# SurfaceEEG_V1_3.net
KiCad netlist of a schematic drawn in EAGLE
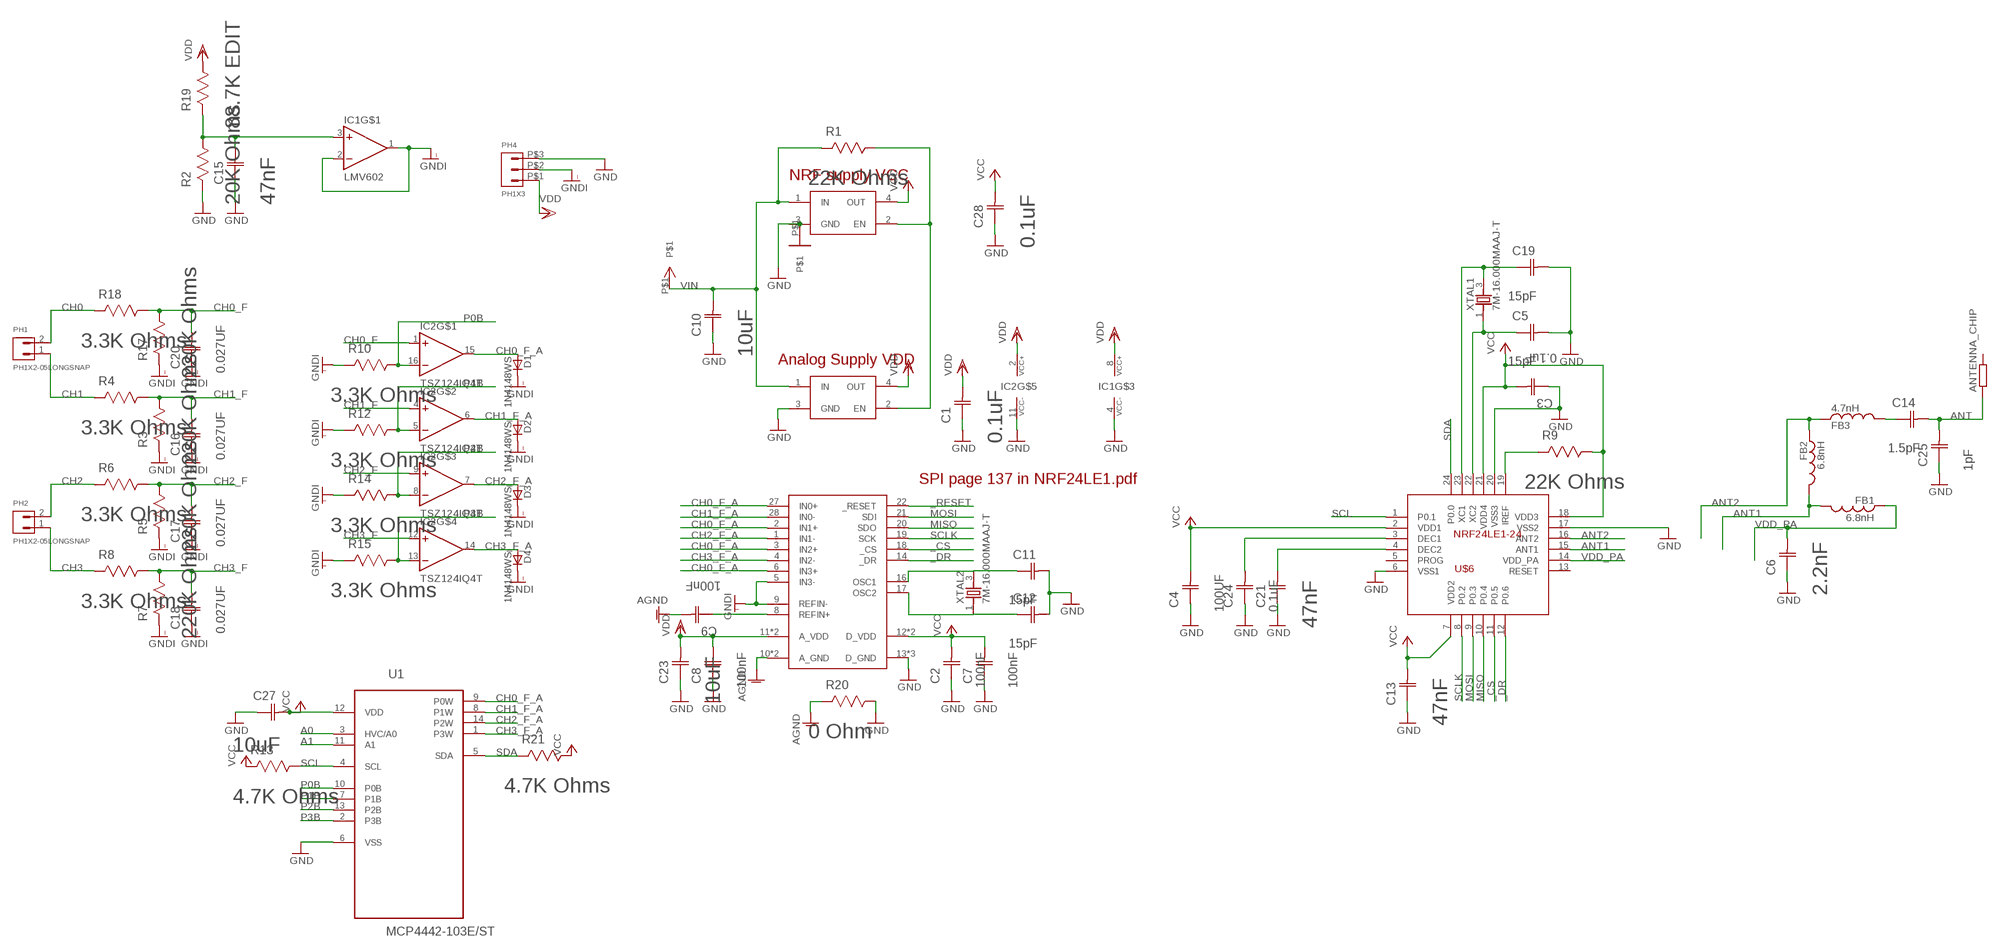
[diagram p0: schematic, sheet 1]

(export (version "E")
  (design (tool "Eeschema 10.0.6"))
  (components
    (comp (ref "ANTENNA_CHIP")
      (value "R0805")
      (footprint "eagle-import:R0805")
      (libsource (lib "eagle-import") (part "R0805"))
    )
    (comp (ref "C1")
      (value "0.1uF")
      (footprint "eagle-import:CAPC1608X85N")
      (fields (field (name "MPN") "C0603C104K5RAC-TU") (field (name "TOLERANCE") "±10%"))
      (libsource (lib "eagle-import") (part "C0603C104K5RAC-TU"))
    )
    (comp (ref "C2")
      (value "100nF")
      (footprint "eagle-import:CAPC1608X90N")
      (fields (field (name "MPN") "06033C104JAT2A") (field (name "TOLERANCE") "±5%"))
      (libsource (lib "eagle-import") (part "06033C104JAT2A"))
    )
    (comp (ref "C3")
      (value "0.1uF")
      (footprint "eagle-import:CAPC1005X60N")
      (fields (field (name "MPN") "04023C104KAT2A") (field (name "TOLERANCE") "±10%"))
      (libsource (lib "eagle-import") (part "04023C104KAT2A"))
    )
    (comp (ref "C4")
      (value "100UF")
      (footprint "eagle-import:CAPC3216X178N")
      (fields (field (name "MPN") "1206YD106MAT2A") (field (name "TOLERANCE") "±20%"))
      (libsource (lib "eagle-import") (part "1206YD106MAT2A"))
    )
    (comp (ref "C5")
      (value "15pF")
      (footprint "eagle-import:CAPC1005X60N")
      (fields (field (name "MPN") "UQCL2A150JAT2A/500") (field (name "TOLERANCE") "±5%"))
      (libsource (lib "eagle-import") (part "UQCL2A150JAT2A/500"))
    )
    (comp (ref "C6")
      (value "2.2nF")
      (footprint "eagle-import:CAPC1005X60N")
      (fields (field (name "MPN") "C0402C222K5RACTU") (field (name "TOLERANCE") "±10%"))
      (libsource (lib "eagle-import") (part "C0402C222K5RACTU"))
    )
    (comp (ref "C7")
      (value "100nF")
      (footprint "eagle-import:CAPC1608X90N")
      (fields (field (name "MPN") "06033C104JAT2A") (field (name "TOLERANCE") "±5%"))
      (libsource (lib "eagle-import") (part "06033C104JAT2A"))
    )
    (comp (ref "C8")
      (value "100nF")
      (footprint "eagle-import:CAPC1608X90N")
      (fields (field (name "MPN") "06033C104JAT2A") (field (name "TOLERANCE") "±5%"))
      (libsource (lib "eagle-import") (part "06033C104JAT2A"))
    )
    (comp (ref "C9")
      (value "100nF")
      (footprint "eagle-import:CAPC1608X90N")
      (fields (field (name "MPN") "06033C104JAT2A") (field (name "TOLERANCE") "±5%"))
      (libsource (lib "eagle-import") (part "06033C104JAT2A"))
    )
    (comp (ref "C10")
      (value "10uF")
      (footprint "eagle-import:CAPC1608X85N")
      (fields (field (name "MPN") "C0603C106M9PACTU") (field (name "TOLERANCE") "±20%"))
      (libsource (lib "eagle-import") (part "C0603C106M9PACTU"))
    )
    (comp (ref "C11")
      (value "15pF")
      (footprint "eagle-import:CAPC1005X60N")
      (fields (field (name "MPN") "UQCL2A150JAT2A/500") (field (name "TOLERANCE") "±5%"))
      (libsource (lib "eagle-import") (part "UQCL2A150JAT2A/500"))
    )
    (comp (ref "C12")
      (value "15pF")
      (footprint "eagle-import:CAPC1005X60N")
      (fields (field (name "MPN") "UQCL2A150JAT2A/500") (field (name "TOLERANCE") "±5%"))
      (libsource (lib "eagle-import") (part "UQCL2A150JAT2A/500"))
    )
    (comp (ref "C13")
      (value "47nF")
      (footprint "eagle-import:CAPC1608X85N")
      (fields (field (name "MPN") "C0603C473K1RACTU") (field (name "TOLERANCE") "±10%"))
      (libsource (lib "eagle-import") (part "C0603C473K1RACTU"))
    )
    (comp (ref "C14")
      (value "1.5pF")
      (footprint "eagle-import:CAPC1005X60N")
      (fields (field (name "MPN") "UQCL2A1R5BAT2A/500") (field (name "TOLERANCE") "±.1 pF"))
      (libsource (lib "eagle-import") (part "UQCL2A1R5BAT2A/500"))
    )
    (comp (ref "C15")
      (value "47nF")
      (footprint "eagle-import:CAPC1608X85N")
      (fields (field (name "MPN") "C0603C473K1RACTU") (field (name "TOLERANCE") "±10%"))
      (libsource (lib "eagle-import") (part "C0603C473K1RACTU"))
    )
    (comp (ref "C16")
      (value "0.027UF")
      (footprint "eagle-import:CAPC1608X90N")
      (fields (field (name "MPN") "0603YC273JAT2A") (field (name "TOLERANCE") "±5%"))
      (libsource (lib "eagle-import") (part "0603YC273JAT2A"))
    )
    (comp (ref "C17")
      (value "0.027UF")
      (footprint "eagle-import:CAPC1608X90N")
      (fields (field (name "MPN") "0603YC273JAT2A") (field (name "TOLERANCE") "±5%"))
      (libsource (lib "eagle-import") (part "0603YC273JAT2A"))
    )
    (comp (ref "C18")
      (value "0.027UF")
      (footprint "eagle-import:CAPC1608X90N")
      (fields (field (name "MPN") "0603YC273JAT2A") (field (name "TOLERANCE") "±5%"))
      (libsource (lib "eagle-import") (part "0603YC273JAT2A"))
    )
    (comp (ref "C19")
      (value "15pF")
      (footprint "eagle-import:CAPC1005X60N")
      (fields (field (name "MPN") "UQCL2A150JAT2A/500") (field (name "TOLERANCE") "±5%"))
      (libsource (lib "eagle-import") (part "UQCL2A150JAT2A/500"))
    )
    (comp (ref "C20")
      (value "0.027UF")
      (footprint "eagle-import:CAPC1608X90N")
      (fields (field (name "MPN") "0603YC273JAT2A") (field (name "TOLERANCE") "±5%"))
      (libsource (lib "eagle-import") (part "0603YC273JAT2A"))
    )
    (comp (ref "C21")
      (value "47nF")
      (footprint "eagle-import:CAPC1608X85N")
      (fields (field (name "MPN") "C0603C473K1RACTU") (field (name "TOLERANCE") "±10%"))
      (libsource (lib "eagle-import") (part "C0603C473K1RACTU"))
    )
    (comp (ref "C23")
      (value "10uF")
      (footprint "eagle-import:CAPC1608X85N")
      (fields (field (name "MPN") "C0603C106M9PACTU") (field (name "TOLERANCE") "±20%"))
      (libsource (lib "eagle-import") (part "C0603C106M9PACTU"))
    )
    (comp (ref "C24")
      (value "0.1uF")
      (footprint "eagle-import:CAPC1005X60N")
      (fields (field (name "MPN") "04023C104KAT2A") (field (name "TOLERANCE") "±10%"))
      (libsource (lib "eagle-import") (part "04023C104KAT2A"))
    )
    (comp (ref "C25")
      (value "1pF")
      (footprint "eagle-import:CAPC1005X60N")
      (fields (field (name "MPN") "UQCL2A1R0BAT2A/500") (field (name "TOLERANCE") "±.1 pF"))
      (libsource (lib "eagle-import") (part "UQCL2A1R0BAT2A/500"))
    )
    (comp (ref "C27")
      (value "10uF")
      (footprint "eagle-import:CAPC1608X85N")
      (fields (field (name "MPN") "C0603C106M9PACTU") (field (name "TOLERANCE") "±20%"))
      (libsource (lib "eagle-import") (part "C0603C106M9PACTU"))
    )
    (comp (ref "C28")
      (value "0.1uF")
      (footprint "eagle-import:CAPC1608X85N")
      (fields (field (name "MPN") "C0603C104K5RAC-TU") (field (name "TOLERANCE") "±10%"))
      (libsource (lib "eagle-import") (part "C0603C104K5RAC-TU"))
    )
    (comp (ref "D1")
      (value "1N4148WS")
      (footprint "eagle-import:SOD323F")
      (libsource (lib "eagle-import") (part "1N4148WS"))
    )
    (comp (ref "D2")
      (value "1N4148WS")
      (footprint "eagle-import:SOD323F")
      (libsource (lib "eagle-import") (part "1N4148WS"))
    )
    (comp (ref "D3")
      (value "1N4148WS")
      (footprint "eagle-import:SOD323F")
      (libsource (lib "eagle-import") (part "1N4148WS"))
    )
    (comp (ref "D4")
      (value "1N4148WS")
      (footprint "eagle-import:SOD323F")
      (libsource (lib "eagle-import") (part "1N4148WS"))
    )
    (comp (ref "FB1")
      (value "6.8nH")
      (footprint "eagle-import:FB0402")
      (libsource (lib "eagle-import") (part "FB0402"))
    )
    (comp (ref "FB2")
      (value "6.8nH")
      (footprint "eagle-import:FB0402")
      (libsource (lib "eagle-import") (part "FB0402"))
    )
    (comp (ref "FB3")
      (value "4.7nH")
      (footprint "eagle-import:FB0402")
      (libsource (lib "eagle-import") (part "FB0402"))
    )
    (comp (ref "IC1")
      (value "LMV602")
      (footprint "eagle-import:VSSOP8")
      (fields (field (name "MPN") "LMV602MM/NOPB"))
      (libsource (lib "eagle-import") (part "LMV602"))
    )
    (comp (ref "IC2")
      (value "TSZ124IQ4T")
      (footprint "eagle-import:QFN16")
      (libsource (lib "eagle-import") (part "TSZ124IQ4T"))
    )
    (comp (ref "PH1")
      (value "PH1X2-05LONGSNAP")
      (footprint "eagle-import:PHLS005-1-2")
      (libsource (lib "eagle-import") (part "PH1X2-05LONGSNAP"))
    )
    (comp (ref "PH2")
      (value "PH1X2-05LONGSNAP")
      (footprint "eagle-import:PHLS005-1-2")
      (libsource (lib "eagle-import") (part "PH1X2-05LONGSNAP"))
    )
    (comp (ref "PH4")
      (value "PH1X3")
      (footprint "eagle-import:PH005-1-3")
      (libsource (lib "eagle-import") (part "PH1X3"))
    )
    (comp (ref "R1")
      (value "22K Ohms")
      (footprint "eagle-import:RESC1608X60N")
      (fields (field (name "MPN") "RC0603FR-0722KL") (field (name "TOLERANCE") "±1%"))
      (libsource (lib "eagle-import") (part "RC0603FR-0722KL"))
    )
    (comp (ref "R2")
      (value "20K Ohms")
      (footprint "eagle-import:RESC1608X60N")
      (fields (field (name "MPN") "RC0603FR-0720KL") (field (name "TOLERANCE") "±1%"))
      (libsource (lib "eagle-import") (part "RC0603FR-0720KL"))
    )
    (comp (ref "R3")
      (value "220K Ohms")
      (footprint "eagle-import:RESC1608X60N")
      (fields (field (name "MPN") "RC0603FR-07220KL") (field (name "TOLERANCE") "±1%"))
      (libsource (lib "eagle-import") (part "RC0603FR-07220KL"))
    )
    (comp (ref "R4")
      (value "3.3K Ohms")
      (footprint "eagle-import:RESC1608X60N")
      (fields (field (name "MPN") "RC0603FR-073K3L") (field (name "TOLERANCE") "±1%"))
      (libsource (lib "eagle-import") (part "RC0603FR-073K3L"))
    )
    (comp (ref "R5")
      (value "220K Ohms")
      (footprint "eagle-import:RESC1608X60N")
      (fields (field (name "MPN") "RC0603FR-07220KL") (field (name "TOLERANCE") "±1%"))
      (libsource (lib "eagle-import") (part "RC0603FR-07220KL"))
    )
    (comp (ref "R6")
      (value "3.3K Ohms")
      (footprint "eagle-import:RESC1608X60N")
      (fields (field (name "MPN") "RC0603FR-073K3L") (field (name "TOLERANCE") "±1%"))
      (libsource (lib "eagle-import") (part "RC0603FR-073K3L"))
    )
    (comp (ref "R7")
      (value "220K Ohms")
      (footprint "eagle-import:RESC1608X60N")
      (fields (field (name "MPN") "RC0603FR-07220KL") (field (name "TOLERANCE") "±1%"))
      (libsource (lib "eagle-import") (part "RC0603FR-07220KL"))
    )
    (comp (ref "R8")
      (value "3.3K Ohms")
      (footprint "eagle-import:RESC1608X60N")
      (fields (field (name "MPN") "RC0603FR-073K3L") (field (name "TOLERANCE") "±1%"))
      (libsource (lib "eagle-import") (part "RC0603FR-073K3L"))
    )
    (comp (ref "R9")
      (value "22K Ohms")
      (footprint "eagle-import:RESC1608X60N")
      (fields (field (name "MPN") "RC0603FR-0722KL") (field (name "TOLERANCE") "±1%"))
      (libsource (lib "eagle-import") (part "RC0603FR-0722KL"))
    )
    (comp (ref "R10")
      (value "3.3K Ohms")
      (footprint "eagle-import:RESC1608X60N")
      (fields (field (name "MPN") "RC0603FR-073K3L") (field (name "TOLERANCE") "±1%"))
      (libsource (lib "eagle-import") (part "RC0603FR-073K3L"))
    )
    (comp (ref "R12")
      (value "3.3K Ohms")
      (footprint "eagle-import:RESC1608X60N")
      (fields (field (name "MPN") "RC0603FR-073K3L") (field (name "TOLERANCE") "±1%"))
      (libsource (lib "eagle-import") (part "RC0603FR-073K3L"))
    )
    (comp (ref "R13")
      (value "4.7K Ohms")
      (footprint "eagle-import:RESC1005X40N")
      (fields (field (name "MPN") "9C04021A4701JLHF3") (field (name "TOLERANCE") "±5%"))
      (libsource (lib "eagle-import") (part "9C04021A4701JLHF3"))
    )
    (comp (ref "R14")
      (value "3.3K Ohms")
      (footprint "eagle-import:RESC1608X60N")
      (fields (field (name "MPN") "RC0603FR-073K3L") (field (name "TOLERANCE") "±1%"))
      (libsource (lib "eagle-import") (part "RC0603FR-073K3L"))
    )
    (comp (ref "R15")
      (value "3.3K Ohms")
      (footprint "eagle-import:RESC1608X60N")
      (fields (field (name "MPN") "RC0603FR-073K3L") (field (name "TOLERANCE") "±1%"))
      (libsource (lib "eagle-import") (part "RC0603FR-073K3L"))
    )
    (comp (ref "R17")
      (value "220K Ohms")
      (footprint "eagle-import:RESC1608X60N")
      (fields (field (name "MPN") "RC0603FR-07220KL") (field (name "TOLERANCE") "±1%"))
      (libsource (lib "eagle-import") (part "RC0603FR-07220KL"))
    )
    (comp (ref "R18")
      (value "3.3K Ohms")
      (footprint "eagle-import:RESC1608X60N")
      (fields (field (name "MPN") "RC0603FR-073K3L") (field (name "TOLERANCE") "±1%"))
      (libsource (lib "eagle-import") (part "RC0603FR-073K3L"))
    )
    (comp (ref "R19")
      (value "88.7K EDIT")
      (footprint "eagle-import:RESC1608X60N")
      (fields (field (name "MPN") "RT0603FRE0782KL") (field (name "TOLERANCE") "±1%"))
      (libsource (lib "eagle-import") (part "RT0603FRE0782KL"))
    )
    (comp (ref "R20")
      (value "0 Ohm")
      (footprint "eagle-import:RESC1608X60N")
      (fields (field (name "MPN") "9C06031A0R00JLHFT") (field (name "TOLERANCE") "±5%"))
      (libsource (lib "eagle-import") (part "9C06031A0R00JLHFT"))
    )
    (comp (ref "R21")
      (value "4.7K Ohms")
      (footprint "eagle-import:RESC1005X40N")
      (fields (field (name "MPN") "9C04021A4701JLHF3") (field (name "TOLERANCE") "±5%"))
      (libsource (lib "eagle-import") (part "9C04021A4701JLHF3"))
    )
    (comp (ref "U$1")
      (value "NCP103")
      (footprint "eagle-import:UDFN4-1_1")
      (fields (field (name "MPN") "NCP103AMX330TCG"))
      (libsource (lib "eagle-import") (part "NCP103"))
    )
    (comp (ref "U$2")
      (value "NCP103")
      (footprint "eagle-import:UDFN4-1_1")
      (fields (field (name "MPN") "NCP103AMX330TCG"))
      (libsource (lib "eagle-import") (part "NCP103"))
    )
    (comp (ref "U$3")
      (value "MCP3912")
      (footprint "eagle-import:QFN28")
      (fields (field (name "MPN") "MCP3912A1-E/MQ "))
      (libsource (lib "eagle-import") (part "MCP3912"))
    )
    (comp (ref "U$4")
      (value "VCC")
      (footprint "eagle-import:VCC-PAD")
      (libsource (lib "eagle-import") (part "VCC"))
    )
    (comp (ref "U$5")
      (value "GND")
      (footprint "eagle-import:GND-PAD")
      (libsource (lib "eagle-import") (part "GND"))
    )
    (comp (ref "U$6")
      (value "NRF24LE1-24")
      (footprint "eagle-import:QFN24G-0.5-4X4MM")
      (fields (field (name "MPN") "NRF24LE1-F16Q24"))
      (libsource (lib "eagle-import") (part "NRF24LE1-24"))
    )
    (comp (ref "U1")
      (value "MCP4442-103E/ST")
      (footprint "eagle-import:SOP65P640X120-14N")
      (libsource (lib "eagle-import") (part "MCP4442-103E/ST"))
    )
    (comp (ref "XTAL1")
      (value "7M-16.000MAAJ-T")
      (footprint "eagle-import:TXC_7M-16.000MAAJ-T")
      (fields (field (name "MPN") "7M-16.000MAAJ-T "))
      (libsource (lib "eagle-import") (part "7M-16.000MAAJ-T"))
    )
    (comp (ref "XTAL2")
      (value "7M-16.000MAAJ-T")
      (footprint "eagle-import:TXC_7M-16.000MAAJ-T")
      (fields (field (name "MPN") "7M-16.000MAAJ-T "))
      (libsource (lib "eagle-import") (part "7M-16.000MAAJ-T"))
    )
  )
  (nets
    (net (code "1") (name "/A0") (class "Default")
      (node (ref "U1") (pin "3") (pinfunction "HVC/A0_3") (pintype "input"))
    )
    (net (code "2") (name "/A1") (class "Default")
      (node (ref "U1") (pin "11") (pinfunction "A1_11") (pintype "input"))
    )
    (net (code "3") (name "/ANT") (class "Default")
      (node (ref "ANTENNA_CHIP") (pin "1") (pinfunction "1_1") (pintype "passive"))
      (node (ref "C14") (pin "1") (pinfunction "C2_1") (pintype "passive"))
      (node (ref "C25") (pin "1") (pinfunction "C2_1") (pintype "passive"))
    )
    (net (code "4") (name "/ANT1") (class "Default")
      (node (ref "FB1") (pin "2") (pinfunction "2_2") (pintype "passive"))
      (node (ref "FB2") (pin "2") (pinfunction "2_2") (pintype "passive"))
      (node (ref "U$6") (pin "15") (pinfunction "ANT1_15") (pintype "bidirectional"))
    )
    (net (code "5") (name "/ANT2") (class "Default")
      (node (ref "FB2") (pin "1") (pinfunction "1_1") (pintype "passive"))
      (node (ref "FB3") (pin "1") (pinfunction "1_1") (pintype "passive"))
      (node (ref "U$6") (pin "16") (pinfunction "ANT2_16") (pintype "bidirectional"))
    )
    (net (code "6") (name "/CH0") (class "Default")
      (node (ref "PH1") (pin "2") (pinfunction "2_2") (pintype "bidirectional"))
      (node (ref "R18") (pin "2") (pinfunction "R2_2") (pintype "passive"))
    )
    (net (code "7") (name "/CH0_F") (class "Default")
      (node (ref "C20") (pin "2") (pinfunction "C2_2") (pintype "passive"))
      (node (ref "IC2") (pin "1") (pinfunction "IN+_1") (pintype "input"))
      (node (ref "R17") (pin "1") (pinfunction "R1_1") (pintype "passive"))
      (node (ref "R18") (pin "1") (pinfunction "R1_1") (pintype "passive"))
    )
    (net (code "8") (name "/CH0_F_A") (class "Default")
      (node (ref "D1") (pin "A") (pinfunction "A_A") (pintype "passive"))
      (node (ref "IC2") (pin "15") (pinfunction "OUT_15") (pintype "output"))
      (node (ref "U$3") (pin "2") (pinfunction "IN1+_2") (pintype "bidirectional"))
      (node (ref "U$3") (pin "27") (pinfunction "IN0+_27") (pintype "bidirectional"))
      (node (ref "U$3") (pin "3") (pinfunction "IN2+_3") (pintype "bidirectional"))
      (node (ref "U$3") (pin "6") (pinfunction "IN3+_6") (pintype "bidirectional"))
      (node (ref "U1") (pin "9") (pinfunction "P0W_9") (pintype "passive"))
    )
    (net (code "9") (name "/CH1") (class "Default")
      (node (ref "PH1") (pin "1") (pinfunction "1_1") (pintype "bidirectional"))
      (node (ref "R4") (pin "2") (pinfunction "R2_2") (pintype "passive"))
    )
    (net (code "10") (name "/CH1_F") (class "Default")
      (node (ref "C16") (pin "2") (pinfunction "C2_2") (pintype "passive"))
      (node (ref "IC2") (pin "4") (pinfunction "IN+_4") (pintype "input"))
      (node (ref "R3") (pin "1") (pinfunction "R1_1") (pintype "passive"))
      (node (ref "R4") (pin "1") (pinfunction "R1_1") (pintype "passive"))
    )
    (net (code "11") (name "/CH1_F_A") (class "Default")
      (node (ref "D2") (pin "A") (pinfunction "A_A") (pintype "passive"))
      (node (ref "IC2") (pin "6") (pinfunction "OUT_6") (pintype "output"))
      (node (ref "U$3") (pin "28") (pinfunction "IN0-_28") (pintype "bidirectional"))
      (node (ref "U1") (pin "8") (pinfunction "P1W_8") (pintype "passive"))
    )
    (net (code "12") (name "/CH2") (class "Default")
      (node (ref "PH2") (pin "2") (pinfunction "2_2") (pintype "bidirectional"))
      (node (ref "R6") (pin "2") (pinfunction "R2_2") (pintype "passive"))
    )
    (net (code "13") (name "/CH2_F") (class "Default")
      (node (ref "C17") (pin "2") (pinfunction "C2_2") (pintype "passive"))
      (node (ref "IC2") (pin "9") (pinfunction "IN+_9") (pintype "input"))
      (node (ref "R5") (pin "1") (pinfunction "R1_1") (pintype "passive"))
      (node (ref "R6") (pin "1") (pinfunction "R1_1") (pintype "passive"))
    )
    (net (code "14") (name "/CH2_F_A") (class "Default")
      (node (ref "D3") (pin "A") (pinfunction "A_A") (pintype "passive"))
      (node (ref "IC2") (pin "7") (pinfunction "OUT_7") (pintype "output"))
      (node (ref "U$3") (pin "1") (pinfunction "IN1-_1") (pintype "bidirectional"))
      (node (ref "U1") (pin "14") (pinfunction "P2W_14") (pintype "passive"))
    )
    (net (code "15") (name "/CH3") (class "Default")
      (node (ref "PH2") (pin "1") (pinfunction "1_1") (pintype "bidirectional"))
      (node (ref "R8") (pin "2") (pinfunction "R2_2") (pintype "passive"))
    )
    (net (code "16") (name "/CH3_F") (class "Default")
      (node (ref "C18") (pin "2") (pinfunction "C2_2") (pintype "passive"))
      (node (ref "IC2") (pin "12") (pinfunction "IN+_12") (pintype "input"))
      (node (ref "R7") (pin "1") (pinfunction "R1_1") (pintype "passive"))
      (node (ref "R8") (pin "1") (pinfunction "R1_1") (pintype "passive"))
    )
    (net (code "17") (name "/CH3_F_A") (class "Default")
      (node (ref "D4") (pin "A") (pinfunction "A_A") (pintype "passive"))
      (node (ref "IC2") (pin "14") (pinfunction "OUT_14") (pintype "output"))
      (node (ref "U$3") (pin "4") (pinfunction "IN2-_4") (pintype "bidirectional"))
      (node (ref "U1") (pin "1") (pinfunction "P3W_1") (pintype "passive"))
    )
    (net (code "18") (name "/MISO") (class "Default")
      (node (ref "U$3") (pin "20") (pinfunction "SDO_20") (pintype "bidirectional"))
      (node (ref "U$6") (pin "10") (pinfunction "P0.4_10") (pintype "bidirectional"))
    )
    (net (code "19") (name "/MOSI") (class "Default")
      (node (ref "U$3") (pin "21") (pinfunction "SDI_21") (pintype "bidirectional"))
      (node (ref "U$6") (pin "9") (pinfunction "P0.3_9") (pintype "bidirectional"))
    )
    (net (code "20") (name "/P0B") (class "Default")
      (node (ref "IC2") (pin "16") (pinfunction "IN-_16") (pintype "input"))
      (node (ref "R10") (pin "1") (pinfunction "R1_1") (pintype "passive"))
      (node (ref "U1") (pin "10") (pinfunction "P0B_10") (pintype "passive"))
    )
    (net (code "21") (name "/P1B") (class "Default")
      (node (ref "IC2") (pin "5") (pinfunction "IN-_5") (pintype "input"))
      (node (ref "R12") (pin "1") (pinfunction "R1_1") (pintype "passive"))
      (node (ref "U1") (pin "7") (pinfunction "P1B_7") (pintype "passive"))
    )
    (net (code "22") (name "/P2B") (class "Default")
      (node (ref "IC2") (pin "8") (pinfunction "IN-_8") (pintype "input"))
      (node (ref "R14") (pin "1") (pinfunction "R1_1") (pintype "passive"))
      (node (ref "U1") (pin "13") (pinfunction "P2B_13") (pintype "passive"))
    )
    (net (code "23") (name "/P3B") (class "Default")
      (node (ref "IC2") (pin "13") (pinfunction "IN-_13") (pintype "input"))
      (node (ref "R15") (pin "1") (pinfunction "R1_1") (pintype "passive"))
      (node (ref "U1") (pin "2") (pinfunction "P3B_2") (pintype "passive"))
    )
    (net (code "24") (name "/SCL") (class "Default")
      (node (ref "R13") (pin "1") (pinfunction "R1_1") (pintype "passive"))
      (node (ref "U$6") (pin "1") (pinfunction "P0.1_1") (pintype "bidirectional"))
      (node (ref "U1") (pin "4") (pinfunction "SCL_4") (pintype "input"))
    )
    (net (code "25") (name "/SCLK") (class "Default")
      (node (ref "U$3") (pin "19") (pinfunction "SCK_19") (pintype "bidirectional"))
      (node (ref "U$6") (pin "8") (pinfunction "P0.2_8") (pintype "bidirectional"))
    )
    (net (code "26") (name "/SDA") (class "Default")
      (node (ref "R21") (pin "2") (pinfunction "R2_2") (pintype "passive"))
      (node (ref "U$6") (pin "24") (pinfunction "P0.0_24") (pintype "bidirectional"))
      (node (ref "U1") (pin "5") (pinfunction "SDA_5") (pintype "bidirectional"))
    )
    (net (code "27") (name "/VDD_PA") (class "Default")
      (node (ref "C6") (pin "2") (pinfunction "C2_2") (pintype "passive"))
      (node (ref "FB1") (pin "1") (pinfunction "1_1") (pintype "passive"))
      (node (ref "U$6") (pin "14") (pinfunction "VDD_PA_14") (pintype "bidirectional"))
    )
    (net (code "28") (name "/VIN") (class "Default")
      (node (ref "C10") (pin "2") (pinfunction "C2_2") (pintype "passive"))
      (node (ref "R1") (pin "2") (pinfunction "R2_2") (pintype "passive"))
      (node (ref "U$1") (pin "1") (pinfunction "IN_1") (pintype "bidirectional"))
      (node (ref "U$2") (pin "1") (pinfunction "IN_1") (pintype "bidirectional"))
      (node (ref "U$4") (pin "P$1") (pinfunction "P$1_P$1") (pintype "bidirectional"))
    )
    (net (code "29") (name "/_CS") (class "Default")
      (node (ref "U$3") (pin "18") (pinfunction "_CS_18") (pintype "bidirectional"))
      (node (ref "U$6") (pin "11") (pinfunction "P0.5_11") (pintype "bidirectional"))
    )
    (net (code "30") (name "/_DR") (class "Default")
      (node (ref "U$3") (pin "14") (pinfunction "_DR_14") (pintype "bidirectional"))
      (node (ref "U$6") (pin "12") (pinfunction "P0.6_12") (pintype "bidirectional"))
    )
    (net (code "31") (name "/_RESET") (class "Default")
      (node (ref "U$3") (pin "22") (pinfunction "_RESET_22") (pintype "bidirectional"))
    )
    (net (code "32") (name "AGND") (class "Default")
      (node (ref "C9") (pin "2") (pinfunction "C2_2") (pintype "passive"))
      (node (ref "R20") (pin "2") (pinfunction "R2_2") (pintype "passive"))
      (node (ref "U$3") (pin "10") (pinfunction "A_GND_10") (pintype "bidirectional"))
      (node (ref "U$3") (pin "26") (pinfunction "A_GND_26") (pintype "bidirectional"))
    )
    (net (code "33") (name "GND") (class "Default")
      (node (ref "C1") (pin "1") (pinfunction "C1_1") (pintype "passive"))
      (node (ref "C10") (pin "1") (pinfunction "C1_1") (pintype "passive"))
      (node (ref "C11") (pin "1") (pinfunction "C2_1") (pintype "passive"))
      (node (ref "C12") (pin "1") (pinfunction "C2_1") (pintype "passive"))
      (node (ref "C13") (pin "1") (pinfunction "C1_1") (pintype "passive"))
      (node (ref "C15") (pin "1") (pinfunction "C1_1") (pintype "passive"))
      (node (ref "C19") (pin "1") (pinfunction "C2_1") (pintype "passive"))
      (node (ref "C2") (pin "1") (pinfunction "C1_1") (pintype "passive"))
      (node (ref "C21") (pin "1") (pinfunction "C1_1") (pintype "passive"))
      (node (ref "C23") (pin "1") (pinfunction "C1_1") (pintype "passive"))
      (node (ref "C24") (pin "2") (pinfunction "C1_2") (pintype "passive"))
      (node (ref "C25") (pin "2") (pinfunction "C1_2") (pintype "passive"))
      (node (ref "C27") (pin "1") (pinfunction "C1_1") (pintype "passive"))
      (node (ref "C28") (pin "1") (pinfunction "C1_1") (pintype "passive"))
      (node (ref "C3") (pin "2") (pinfunction "C1_2") (pintype "passive"))
      (node (ref "C4") (pin "1") (pinfunction "C1_1") (pintype "passive"))
      (node (ref "C5") (pin "1") (pinfunction "C2_1") (pintype "passive"))
      (node (ref "C6") (pin "1") (pinfunction "C1_1") (pintype "passive"))
      (node (ref "C7") (pin "1") (pinfunction "C1_1") (pintype "passive"))
      (node (ref "C8") (pin "1") (pinfunction "C1_1") (pintype "passive"))
      (node (ref "IC1") (pin "4") (pinfunction "VCC-_4") (pintype "power_in"))
      (node (ref "IC2") (pin "11") (pinfunction "VCC-_11") (pintype "power_in"))
      (node (ref "PH4") (pin "P$3") (pinfunction "3_P$3") (pintype "bidirectional"))
      (node (ref "R2") (pin "2") (pinfunction "R2_2") (pintype "passive"))
      (node (ref "R20") (pin "1") (pinfunction "R1_1") (pintype "passive"))
      (node (ref "U$1") (pin "3") (pinfunction "GND_3") (pintype "bidirectional"))
      (node (ref "U$2") (pin "3") (pinfunction "GND_3") (pintype "bidirectional"))
      (node (ref "U$3") (pin "13") (pinfunction "D_GND_13") (pintype "bidirectional"))
      (node (ref "U$3") (pin "15") (pinfunction "D_GND_15") (pintype "bidirectional"))
      (node (ref "U$3") (pin "23") (pinfunction "D_GND_23") (pintype "bidirectional"))
      (node (ref "U$5") (pin "P$1") (pinfunction "P$1_P$1") (pintype "bidirectional"))
      (node (ref "U$6") (pin "17") (pinfunction "VSS2_17") (pintype "bidirectional"))
      (node (ref "U$6") (pin "20") (pinfunction "VSS3_20") (pintype "bidirectional"))
      (node (ref "U$6") (pin "6") (pinfunction "VSS1_6") (pintype "bidirectional"))
      (node (ref "U1") (pin "6") (pinfunction "VSS_6") (pintype "power_in"))
    )
    (net (code "34") (name "GNDI") (class "Default")
      (node (ref "C16") (pin "1") (pinfunction "C1_1") (pintype "passive"))
      (node (ref "C17") (pin "1") (pinfunction "C1_1") (pintype "passive"))
      (node (ref "C18") (pin "1") (pinfunction "C1_1") (pintype "passive"))
      (node (ref "C20") (pin "1") (pinfunction "C1_1") (pintype "passive"))
      (node (ref "D1") (pin "C") (pinfunction "C_C") (pintype "passive"))
      (node (ref "D2") (pin "C") (pinfunction "C_C") (pintype "passive"))
      (node (ref "D3") (pin "C") (pinfunction "C_C") (pintype "passive"))
      (node (ref "D4") (pin "C") (pinfunction "C_C") (pintype "passive"))
      (node (ref "IC1") (pin "1") (pinfunction "OUT_1") (pintype "output"))
      (node (ref "IC1") (pin "2") (pinfunction "IN-_2") (pintype "input"))
      (node (ref "PH4") (pin "P$2") (pinfunction "2_P$2") (pintype "bidirectional"))
      (node (ref "R10") (pin "2") (pinfunction "R2_2") (pintype "passive"))
      (node (ref "R12") (pin "2") (pinfunction "R2_2") (pintype "passive"))
      (node (ref "R14") (pin "2") (pinfunction "R2_2") (pintype "passive"))
      (node (ref "R15") (pin "2") (pinfunction "R2_2") (pintype "passive"))
      (node (ref "R17") (pin "2") (pinfunction "R2_2") (pintype "passive"))
      (node (ref "R3") (pin "2") (pinfunction "R2_2") (pintype "passive"))
      (node (ref "R5") (pin "2") (pinfunction "R2_2") (pintype "passive"))
      (node (ref "R7") (pin "2") (pinfunction "R2_2") (pintype "passive"))
      (node (ref "U$3") (pin "5") (pinfunction "IN3-_5") (pintype "bidirectional"))
      (node (ref "U$3") (pin "9") (pinfunction "REFIN-_9") (pintype "bidirectional"))
    )
    (net (code "35") (name "Net-(C5-C1)") (class "Default")
      (node (ref "C5") (pin "2") (pinfunction "C1_2") (pintype "passive"))
      (node (ref "U$6") (pin "22") (pinfunction "XC2_22") (pintype "bidirectional"))
      (node (ref "XTAL1") (pin "1") (pinfunction "1_1") (pintype "passive"))
    )
    (net (code "36") (name "Net-(C9-C1)") (class "Default")
      (node (ref "C9") (pin "1") (pinfunction "C1_1") (pintype "passive"))
      (node (ref "U$3") (pin "8") (pinfunction "REFIN+_8") (pintype "bidirectional"))
    )
    (net (code "37") (name "Net-(C11-C1)") (class "Default")
      (node (ref "C11") (pin "2") (pinfunction "C1_2") (pintype "passive"))
      (node (ref "U$3") (pin "16") (pinfunction "OSC1_16") (pintype "bidirectional"))
      (node (ref "XTAL2") (pin "3") (pinfunction "3_3") (pintype "passive"))
    )
    (net (code "38") (name "Net-(C12-C1)") (class "Default")
      (node (ref "C12") (pin "2") (pinfunction "C1_2") (pintype "passive"))
      (node (ref "U$3") (pin "17") (pinfunction "OSC2_17") (pintype "bidirectional"))
      (node (ref "XTAL2") (pin "1") (pinfunction "1_1") (pintype "passive"))
    )
    (net (code "39") (name "Net-(C14-C1)") (class "Default")
      (node (ref "C14") (pin "2") (pinfunction "C1_2") (pintype "passive"))
      (node (ref "FB3") (pin "2") (pinfunction "2_2") (pintype "passive"))
    )
    (net (code "40") (name "Net-(C15-C2)") (class "Default")
      (node (ref "C15") (pin "2") (pinfunction "C2_2") (pintype "passive"))
      (node (ref "IC1") (pin "3") (pinfunction "IN+_3") (pintype "input"))
      (node (ref "R19") (pin "2") (pinfunction "R2_2") (pintype "passive"))
      (node (ref "R2") (pin "1") (pinfunction "R1_1") (pintype "passive"))
    )
    (net (code "41") (name "Net-(C19-C1)") (class "Default")
      (node (ref "C19") (pin "2") (pinfunction "C1_2") (pintype "passive"))
      (node (ref "U$6") (pin "23") (pinfunction "XC1_23") (pintype "bidirectional"))
      (node (ref "XTAL1") (pin "3") (pinfunction "3_3") (pintype "passive"))
    )
    (net (code "42") (name "Net-(C21-C2)") (class "Default")
      (node (ref "C21") (pin "2") (pinfunction "C2_2") (pintype "passive"))
      (node (ref "U$6") (pin "4") (pinfunction "DEC2_4") (pintype "bidirectional"))
    )
    (net (code "43") (name "Net-(C24-C2)") (class "Default")
      (node (ref "C24") (pin "1") (pinfunction "C2_1") (pintype "passive"))
      (node (ref "U$6") (pin "3") (pinfunction "DEC1_3") (pintype "bidirectional"))
    )
    (net (code "44") (name "Net-(R1-R1)") (class "Default")
      (node (ref "R1") (pin "1") (pinfunction "R1_1") (pintype "passive"))
      (node (ref "U$1") (pin "2") (pinfunction "EN_2") (pintype "bidirectional"))
      (node (ref "U$2") (pin "2") (pinfunction "EN_2") (pintype "bidirectional"))
    )
    (net (code "45") (name "Net-(R9-R2)") (class "Default")
      (node (ref "R9") (pin "2") (pinfunction "R2_2") (pintype "passive"))
      (node (ref "U$6") (pin "19") (pinfunction "IREF_19") (pintype "bidirectional"))
    )
    (net (code "46") (name "VCC") (class "Default")
      (node (ref "C13") (pin "2") (pinfunction "C2_2") (pintype "passive"))
      (node (ref "C2") (pin "2") (pinfunction "C2_2") (pintype "passive"))
      (node (ref "C27") (pin "2") (pinfunction "C2_2") (pintype "passive"))
      (node (ref "C28") (pin "2") (pinfunction "C2_2") (pintype "passive"))
      (node (ref "C3") (pin "1") (pinfunction "C2_1") (pintype "passive"))
      (node (ref "C4") (pin "2") (pinfunction "C2_2") (pintype "passive"))
      (node (ref "C7") (pin "2") (pinfunction "C2_2") (pintype "passive"))
      (node (ref "R13") (pin "2") (pinfunction "R2_2") (pintype "passive"))
      (node (ref "R21") (pin "1") (pinfunction "R1_1") (pintype "passive"))
      (node (ref "R9") (pin "1") (pinfunction "R1_1") (pintype "passive"))
      (node (ref "U$1") (pin "4") (pinfunction "OUT_4") (pintype "bidirectional"))
      (node (ref "U$3") (pin "12") (pinfunction "D_VDD_12") (pintype "bidirectional"))
      (node (ref "U$3") (pin "24") (pinfunction "D_VDD_24") (pintype "bidirectional"))
      (node (ref "U$6") (pin "18") (pinfunction "VDD3_18") (pintype "bidirectional"))
      (node (ref "U$6") (pin "2") (pinfunction "VDD1_2") (pintype "bidirectional"))
      (node (ref "U$6") (pin "21") (pinfunction "VDD4_21") (pintype "bidirectional"))
      (node (ref "U$6") (pin "7") (pinfunction "VDD2_7") (pintype "bidirectional"))
      (node (ref "U1") (pin "12") (pinfunction "VDD_12") (pintype "power_in"))
    )
    (net (code "47") (name "VDD") (class "Default")
      (node (ref "C1") (pin "2") (pinfunction "C2_2") (pintype "passive"))
      (node (ref "C23") (pin "2") (pinfunction "C2_2") (pintype "passive"))
      (node (ref "C8") (pin "2") (pinfunction "C2_2") (pintype "passive"))
      (node (ref "IC1") (pin "8") (pinfunction "VCC+_8") (pintype "power_in"))
      (node (ref "IC2") (pin "2") (pinfunction "VCC+_2") (pintype "power_in"))
      (node (ref "PH4") (pin "P$1") (pinfunction "1_P$1") (pintype "bidirectional"))
      (node (ref "R19") (pin "1") (pinfunction "R1_1") (pintype "passive"))
      (node (ref "U$2") (pin "4") (pinfunction "OUT_4") (pintype "bidirectional"))
      (node (ref "U$3") (pin "11") (pinfunction "A_VDD_11") (pintype "bidirectional"))
      (node (ref "U$3") (pin "25") (pinfunction "A_VDD_25") (pintype "bidirectional"))
    )
    (net (code "48") (name "unconnected-(ANTENNA_CHIP-Pad2)") (class "Default")
      (node (ref "ANTENNA_CHIP") (pin "2") (pinfunction "2_2") (pintype "passive"))
    )
    (net (code "49") (name "unconnected-(U$6-PROG-Pad5)") (class "Default")
      (node (ref "U$6") (pin "5") (pinfunction "PROG_5") (pintype "bidirectional"))
    )
    (net (code "50") (name "unconnected-(U$6-RESET-Pad13)") (class "Default")
      (node (ref "U$6") (pin "13") (pinfunction "RESET_13") (pintype "bidirectional"))
    )
  )
)
